# audio_mixer.net
KiCad netlist of a schematic drawn in EAGLE
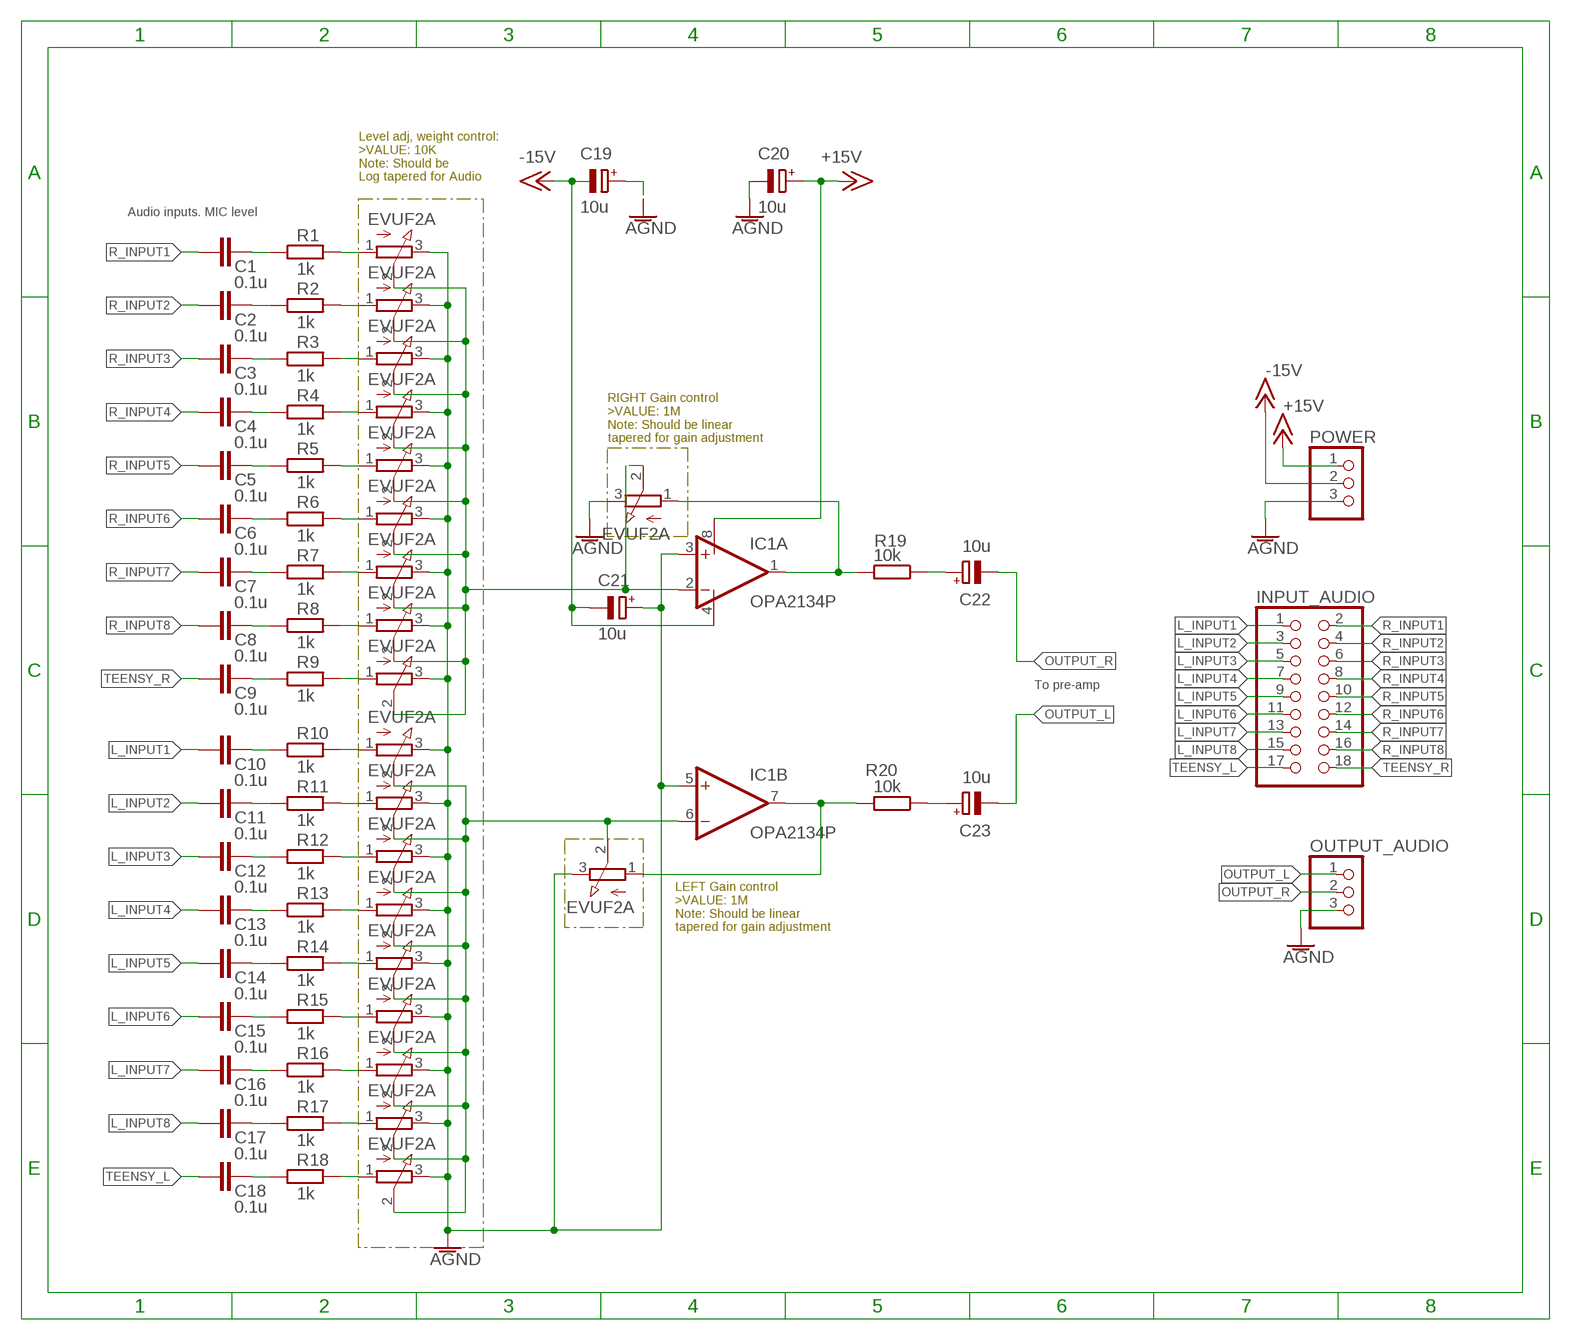
[diagram p0: schematic, sheet 1]

(export (version "E")
  (design (tool "Eeschema 10.0.6"))
  (components
    (comp (ref "C1")
      (value "0.1u")
      (footprint "eagle-import:C025-030X050")
      (libsource (lib "eagle-import") (part "C-EU025-030X050"))
    )
    (comp (ref "C2")
      (value "0.1u")
      (footprint "eagle-import:C025-030X050")
      (libsource (lib "eagle-import") (part "C-EU025-030X050"))
    )
    (comp (ref "C3")
      (value "0.1u")
      (footprint "eagle-import:C025-030X050")
      (libsource (lib "eagle-import") (part "C-EU025-030X050"))
    )
    (comp (ref "C4")
      (value "0.1u")
      (footprint "eagle-import:C025-030X050")
      (libsource (lib "eagle-import") (part "C-EU025-030X050"))
    )
    (comp (ref "C5")
      (value "0.1u")
      (footprint "eagle-import:C025-030X050")
      (libsource (lib "eagle-import") (part "C-EU025-030X050"))
    )
    (comp (ref "C6")
      (value "0.1u")
      (footprint "eagle-import:C025-030X050")
      (libsource (lib "eagle-import") (part "C-EU025-030X050"))
    )
    (comp (ref "C7")
      (value "0.1u")
      (footprint "eagle-import:C025-030X050")
      (libsource (lib "eagle-import") (part "C-EU025-030X050"))
    )
    (comp (ref "C8")
      (value "0.1u")
      (footprint "eagle-import:C025-030X050")
      (libsource (lib "eagle-import") (part "C-EU025-030X050"))
    )
    (comp (ref "C9")
      (value "0.1u")
      (footprint "eagle-import:C025-030X050")
      (libsource (lib "eagle-import") (part "C-EU025-030X050"))
    )
    (comp (ref "C10")
      (value "0.1u")
      (footprint "eagle-import:C025-030X050")
      (libsource (lib "eagle-import") (part "C-EU025-030X050"))
    )
    (comp (ref "C11")
      (value "0.1u")
      (footprint "eagle-import:C025-030X050")
      (libsource (lib "eagle-import") (part "C-EU025-030X050"))
    )
    (comp (ref "C12")
      (value "0.1u")
      (footprint "eagle-import:C025-030X050")
      (libsource (lib "eagle-import") (part "C-EU025-030X050"))
    )
    (comp (ref "C13")
      (value "0.1u")
      (footprint "eagle-import:C025-030X050")
      (libsource (lib "eagle-import") (part "C-EU025-030X050"))
    )
    (comp (ref "C14")
      (value "0.1u")
      (footprint "eagle-import:C025-030X050")
      (libsource (lib "eagle-import") (part "C-EU025-030X050"))
    )
    (comp (ref "C15")
      (value "0.1u")
      (footprint "eagle-import:C025-030X050")
      (libsource (lib "eagle-import") (part "C-EU025-030X050"))
    )
    (comp (ref "C16")
      (value "0.1u")
      (footprint "eagle-import:C025-030X050")
      (libsource (lib "eagle-import") (part "C-EU025-030X050"))
    )
    (comp (ref "C17")
      (value "0.1u")
      (footprint "eagle-import:C025-030X050")
      (libsource (lib "eagle-import") (part "C-EU025-030X050"))
    )
    (comp (ref "C18")
      (value "0.1u")
      (footprint "eagle-import:C025-030X050")
      (libsource (lib "eagle-import") (part "C-EU025-030X050"))
    )
    (comp (ref "C19")
      (value "10u")
      (footprint "eagle-import:E5-10,5")
      (libsource (lib "eagle-import") (part "CPOL-EUE5-10.5"))
    )
    (comp (ref "C20")
      (value "10u")
      (footprint "eagle-import:E5-10,5")
      (libsource (lib "eagle-import") (part "CPOL-EUE5-10.5"))
    )
    (comp (ref "C21")
      (value "10u")
      (footprint "eagle-import:E5-10,5")
      (libsource (lib "eagle-import") (part "CPOL-EUE5-10.5"))
    )
    (comp (ref "C22")
      (value "10u")
      (footprint "eagle-import:E5-10,5")
      (libsource (lib "eagle-import") (part "CPOL-EUE5-10.5"))
    )
    (comp (ref "C23")
      (value "10u")
      (footprint "eagle-import:E5-10,5")
      (libsource (lib "eagle-import") (part "CPOL-EUE5-10.5"))
    )
    (comp (ref "IC1")
      (value "OPA2134P")
      (footprint "eagle-import:DIL08")
      (libsource (lib "eagle-import") (part "OPA2134P"))
    )
    (comp (ref "INPUT_AUDIO")
      (value "PINHD-2X9")
      (footprint "eagle-import:2X09")
      (libsource (lib "eagle-import") (part "PINHD-2X9"))
    )
    (comp (ref "OUTPUT_AUDIO")
      (value "PINHD-1X3")
      (footprint "eagle-import:1X03")
      (libsource (lib "eagle-import") (part "PINHD-1X3"))
    )
    (comp (ref "POWER")
      (value "PINHD-1X3")
      (footprint "eagle-import:1X03")
      (libsource (lib "eagle-import") (part "PINHD-1X3"))
    )
    (comp (ref "R1")
      (value "1k")
      (footprint "eagle-import:R0805")
      (libsource (lib "eagle-import") (part "R-EU_R0805"))
    )
    (comp (ref "R2")
      (value "1k")
      (footprint "eagle-import:R0805")
      (libsource (lib "eagle-import") (part "R-EU_R0805"))
    )
    (comp (ref "R3")
      (value "1k")
      (footprint "eagle-import:R0805")
      (libsource (lib "eagle-import") (part "R-EU_R0805"))
    )
    (comp (ref "R4")
      (value "1k")
      (footprint "eagle-import:R0805")
      (libsource (lib "eagle-import") (part "R-EU_R0805"))
    )
    (comp (ref "R5")
      (value "1k")
      (footprint "eagle-import:R0805")
      (libsource (lib "eagle-import") (part "R-EU_R0805"))
    )
    (comp (ref "R6")
      (value "1k")
      (footprint "eagle-import:R0805")
      (libsource (lib "eagle-import") (part "R-EU_R0805"))
    )
    (comp (ref "R7")
      (value "1k")
      (footprint "eagle-import:R0805")
      (libsource (lib "eagle-import") (part "R-EU_R0805"))
    )
    (comp (ref "R8")
      (value "1k")
      (footprint "eagle-import:R0805")
      (libsource (lib "eagle-import") (part "R-EU_R0805"))
    )
    (comp (ref "R9")
      (value "1k")
      (footprint "eagle-import:R0805")
      (libsource (lib "eagle-import") (part "R-EU_R0805"))
    )
    (comp (ref "R10")
      (value "1k")
      (footprint "eagle-import:R0805")
      (libsource (lib "eagle-import") (part "R-EU_R0805"))
    )
    (comp (ref "R11")
      (value "1k")
      (footprint "eagle-import:R0805")
      (libsource (lib "eagle-import") (part "R-EU_R0805"))
    )
    (comp (ref "R12")
      (value "1k")
      (footprint "eagle-import:R0805")
      (libsource (lib "eagle-import") (part "R-EU_R0805"))
    )
    (comp (ref "R13")
      (value "1k")
      (footprint "eagle-import:R0805")
      (libsource (lib "eagle-import") (part "R-EU_R0805"))
    )
    (comp (ref "R14")
      (value "1k")
      (footprint "eagle-import:R0805")
      (libsource (lib "eagle-import") (part "R-EU_R0805"))
    )
    (comp (ref "R15")
      (value "1k")
      (footprint "eagle-import:R0805")
      (libsource (lib "eagle-import") (part "R-EU_R0805"))
    )
    (comp (ref "R16")
      (value "1k")
      (footprint "eagle-import:R0805")
      (libsource (lib "eagle-import") (part "R-EU_R0805"))
    )
    (comp (ref "R17")
      (value "1k")
      (footprint "eagle-import:R0805")
      (libsource (lib "eagle-import") (part "R-EU_R0805"))
    )
    (comp (ref "R18")
      (value "1k")
      (footprint "eagle-import:R0805")
      (libsource (lib "eagle-import") (part "R-EU_R0805"))
    )
    (comp (ref "R19")
      (value "10k")
      (footprint "eagle-import:R0805")
      (libsource (lib "eagle-import") (part "R-EU_R0805"))
    )
    (comp (ref "R20")
      (value "10k")
      (footprint "eagle-import:R0805")
      (libsource (lib "eagle-import") (part "R-EU_R0805"))
    )
    (comp (ref "VR1")
      (value "EVUF2A")
      (footprint "eagle-import:EVUF")
      (libsource (lib "eagle-import") (part "EVUAF2"))
    )
    (comp (ref "VR2")
      (value "EVUF2A")
      (footprint "eagle-import:EVUF")
      (libsource (lib "eagle-import") (part "EVUAF2"))
    )
    (comp (ref "VR3")
      (value "EVUF2A")
      (footprint "eagle-import:EVUF")
      (libsource (lib "eagle-import") (part "EVUAF2"))
    )
    (comp (ref "VR4")
      (value "EVUF2A")
      (footprint "eagle-import:EVUF")
      (libsource (lib "eagle-import") (part "EVUAF2"))
    )
    (comp (ref "VR5")
      (value "EVUF2A")
      (footprint "eagle-import:EVUF")
      (libsource (lib "eagle-import") (part "EVUAF2"))
    )
    (comp (ref "VR6")
      (value "EVUF2A")
      (footprint "eagle-import:EVUF")
      (libsource (lib "eagle-import") (part "EVUAF2"))
    )
    (comp (ref "VR7")
      (value "EVUF2A")
      (footprint "eagle-import:EVUF")
      (libsource (lib "eagle-import") (part "EVUAF2"))
    )
    (comp (ref "VR8")
      (value "EVUF2A")
      (footprint "eagle-import:EVUF")
      (libsource (lib "eagle-import") (part "EVUAF2"))
    )
    (comp (ref "VR9")
      (value "EVUF2A")
      (footprint "eagle-import:EVUF")
      (libsource (lib "eagle-import") (part "EVUAF2"))
    )
    (comp (ref "VR10")
      (value "EVUF2A")
      (footprint "eagle-import:EVUF")
      (libsource (lib "eagle-import") (part "EVUAF2"))
    )
    (comp (ref "VR11")
      (value "EVUF2A")
      (footprint "eagle-import:EVUF")
      (libsource (lib "eagle-import") (part "EVUAF2"))
    )
    (comp (ref "VR12")
      (value "EVUF2A")
      (footprint "eagle-import:EVUF")
      (libsource (lib "eagle-import") (part "EVUAF2"))
    )
    (comp (ref "VR13")
      (value "EVUF2A")
      (footprint "eagle-import:EVUF")
      (libsource (lib "eagle-import") (part "EVUAF2"))
    )
    (comp (ref "VR14")
      (value "EVUF2A")
      (footprint "eagle-import:EVUF")
      (libsource (lib "eagle-import") (part "EVUAF2"))
    )
    (comp (ref "VR15")
      (value "EVUF2A")
      (footprint "eagle-import:EVUF")
      (libsource (lib "eagle-import") (part "EVUAF2"))
    )
    (comp (ref "VR16")
      (value "EVUF2A")
      (footprint "eagle-import:EVUF")
      (libsource (lib "eagle-import") (part "EVUAF2"))
    )
    (comp (ref "VR17")
      (value "EVUF2A")
      (footprint "eagle-import:EVUF")
      (libsource (lib "eagle-import") (part "EVUAF2"))
    )
    (comp (ref "VR18")
      (value "EVUF2A")
      (footprint "eagle-import:EVUF")
      (libsource (lib "eagle-import") (part "EVUAF2"))
    )
    (comp (ref "VR19")
      (value "EVUF2A")
      (footprint "eagle-import:EVUF")
      (libsource (lib "eagle-import") (part "EVUAF2"))
    )
    (comp (ref "VR20")
      (value "EVUF2A")
      (footprint "eagle-import:EVUF")
      (libsource (lib "eagle-import") (part "EVUAF2"))
    )
  )
  (nets
    (net (code "1") (name "+15V") (class "Default")
      (node (ref "C20") (pin "+") (pinfunction "+_+") (pintype "passive"))
      (node (ref "IC1") (pin "8") (pinfunction "V+_8") (pintype "power_in"))
      (node (ref "POWER") (pin "1") (pinfunction "1_1") (pintype "passive"))
    )
    (net (code "2") (name "-15V") (class "Default")
      (node (ref "C19") (pin "-") (pinfunction "-_-") (pintype "passive"))
      (node (ref "C21") (pin "-") (pinfunction "-_-") (pintype "passive"))
      (node (ref "IC1") (pin "4") (pinfunction "V-_4") (pintype "power_in"))
      (node (ref "POWER") (pin "2") (pinfunction "2_2") (pintype "passive"))
    )
    (net (code "3") (name "AGND") (class "Default")
      (node (ref "C19") (pin "+") (pinfunction "+_+") (pintype "passive"))
      (node (ref "C20") (pin "-") (pinfunction "-_-") (pintype "passive"))
      (node (ref "C21") (pin "+") (pinfunction "+_+") (pintype "passive"))
      (node (ref "IC1") (pin "3") (pinfunction "+IN_3") (pintype "input"))
      (node (ref "IC1") (pin "5") (pinfunction "+IN_5") (pintype "input"))
      (node (ref "OUTPUT_AUDIO") (pin "3") (pinfunction "3_3") (pintype "passive"))
      (node (ref "POWER") (pin "3") (pinfunction "3_3") (pintype "passive"))
      (node (ref "VR1") (pin "3") (pinfunction "E_3") (pintype "passive"))
      (node (ref "VR10") (pin "3") (pinfunction "E_3") (pintype "passive"))
      (node (ref "VR11") (pin "3") (pinfunction "E_3") (pintype "passive"))
      (node (ref "VR12") (pin "3") (pinfunction "E_3") (pintype "passive"))
      (node (ref "VR13") (pin "3") (pinfunction "E_3") (pintype "passive"))
      (node (ref "VR14") (pin "3") (pinfunction "E_3") (pintype "passive"))
      (node (ref "VR15") (pin "3") (pinfunction "E_3") (pintype "passive"))
      (node (ref "VR16") (pin "3") (pinfunction "E_3") (pintype "passive"))
      (node (ref "VR17") (pin "3") (pinfunction "E_3") (pintype "passive"))
      (node (ref "VR18") (pin "3") (pinfunction "E_3") (pintype "passive"))
      (node (ref "VR19") (pin "3") (pinfunction "E_3") (pintype "passive"))
      (node (ref "VR2") (pin "3") (pinfunction "E_3") (pintype "passive"))
      (node (ref "VR20") (pin "3") (pinfunction "E_3") (pintype "passive"))
      (node (ref "VR3") (pin "3") (pinfunction "E_3") (pintype "passive"))
      (node (ref "VR4") (pin "3") (pinfunction "E_3") (pintype "passive"))
      (node (ref "VR5") (pin "3") (pinfunction "E_3") (pintype "passive"))
      (node (ref "VR6") (pin "3") (pinfunction "E_3") (pintype "passive"))
      (node (ref "VR7") (pin "3") (pinfunction "E_3") (pintype "passive"))
      (node (ref "VR8") (pin "3") (pinfunction "E_3") (pintype "passive"))
      (node (ref "VR9") (pin "3") (pinfunction "E_3") (pintype "passive"))
    )
    (net (code "4") (name "L_INPUT1") (class "Default")
      (node (ref "C10") (pin "2") (pinfunction "2_2") (pintype "passive"))
      (node (ref "INPUT_AUDIO") (pin "1") (pinfunction "1_1") (pintype "passive"))
    )
    (net (code "5") (name "L_INPUT2") (class "Default")
      (node (ref "C11") (pin "2") (pinfunction "2_2") (pintype "passive"))
      (node (ref "INPUT_AUDIO") (pin "3") (pinfunction "3_3") (pintype "passive"))
    )
    (net (code "6") (name "L_INPUT3") (class "Default")
      (node (ref "C12") (pin "2") (pinfunction "2_2") (pintype "passive"))
      (node (ref "INPUT_AUDIO") (pin "5") (pinfunction "5_5") (pintype "passive"))
    )
    (net (code "7") (name "L_INPUT4") (class "Default")
      (node (ref "C13") (pin "2") (pinfunction "2_2") (pintype "passive"))
      (node (ref "INPUT_AUDIO") (pin "7") (pinfunction "7_7") (pintype "passive"))
    )
    (net (code "8") (name "L_INPUT5") (class "Default")
      (node (ref "C14") (pin "2") (pinfunction "2_2") (pintype "passive"))
      (node (ref "INPUT_AUDIO") (pin "9") (pinfunction "9_9") (pintype "passive"))
    )
    (net (code "9") (name "L_INPUT6") (class "Default")
      (node (ref "C15") (pin "2") (pinfunction "2_2") (pintype "passive"))
      (node (ref "INPUT_AUDIO") (pin "11") (pinfunction "11_11") (pintype "passive"))
    )
    (net (code "10") (name "L_INPUT7") (class "Default")
      (node (ref "C16") (pin "2") (pinfunction "2_2") (pintype "passive"))
      (node (ref "INPUT_AUDIO") (pin "13") (pinfunction "13_13") (pintype "passive"))
    )
    (net (code "11") (name "L_INPUT8") (class "Default")
      (node (ref "C17") (pin "2") (pinfunction "2_2") (pintype "passive"))
      (node (ref "INPUT_AUDIO") (pin "15") (pinfunction "15_15") (pintype "passive"))
    )
    (net (code "12") (name "Net-(C1-Pad1)") (class "Default")
      (node (ref "C1") (pin "1") (pinfunction "1_1") (pintype "passive"))
      (node (ref "R1") (pin "1") (pinfunction "1_1") (pintype "passive"))
    )
    (net (code "13") (name "Net-(C2-Pad1)") (class "Default")
      (node (ref "C2") (pin "1") (pinfunction "1_1") (pintype "passive"))
      (node (ref "R2") (pin "1") (pinfunction "1_1") (pintype "passive"))
    )
    (net (code "14") (name "Net-(C3-Pad1)") (class "Default")
      (node (ref "C3") (pin "1") (pinfunction "1_1") (pintype "passive"))
      (node (ref "R3") (pin "1") (pinfunction "1_1") (pintype "passive"))
    )
    (net (code "15") (name "Net-(C4-Pad1)") (class "Default")
      (node (ref "C4") (pin "1") (pinfunction "1_1") (pintype "passive"))
      (node (ref "R4") (pin "1") (pinfunction "1_1") (pintype "passive"))
    )
    (net (code "16") (name "Net-(C5-Pad1)") (class "Default")
      (node (ref "C5") (pin "1") (pinfunction "1_1") (pintype "passive"))
      (node (ref "R5") (pin "1") (pinfunction "1_1") (pintype "passive"))
    )
    (net (code "17") (name "Net-(C6-Pad1)") (class "Default")
      (node (ref "C6") (pin "1") (pinfunction "1_1") (pintype "passive"))
      (node (ref "R6") (pin "1") (pinfunction "1_1") (pintype "passive"))
    )
    (net (code "18") (name "Net-(C7-Pad1)") (class "Default")
      (node (ref "C7") (pin "1") (pinfunction "1_1") (pintype "passive"))
      (node (ref "R7") (pin "1") (pinfunction "1_1") (pintype "passive"))
    )
    (net (code "19") (name "Net-(C8-Pad1)") (class "Default")
      (node (ref "C8") (pin "1") (pinfunction "1_1") (pintype "passive"))
      (node (ref "R8") (pin "1") (pinfunction "1_1") (pintype "passive"))
    )
    (net (code "20") (name "Net-(C9-Pad1)") (class "Default")
      (node (ref "C9") (pin "1") (pinfunction "1_1") (pintype "passive"))
      (node (ref "R9") (pin "1") (pinfunction "1_1") (pintype "passive"))
    )
    (net (code "21") (name "Net-(C10-Pad1)") (class "Default")
      (node (ref "C10") (pin "1") (pinfunction "1_1") (pintype "passive"))
      (node (ref "R10") (pin "1") (pinfunction "1_1") (pintype "passive"))
    )
    (net (code "22") (name "Net-(C11-Pad1)") (class "Default")
      (node (ref "C11") (pin "1") (pinfunction "1_1") (pintype "passive"))
      (node (ref "R11") (pin "1") (pinfunction "1_1") (pintype "passive"))
    )
    (net (code "23") (name "Net-(C12-Pad1)") (class "Default")
      (node (ref "C12") (pin "1") (pinfunction "1_1") (pintype "passive"))
      (node (ref "R12") (pin "1") (pinfunction "1_1") (pintype "passive"))
    )
    (net (code "24") (name "Net-(C13-Pad1)") (class "Default")
      (node (ref "C13") (pin "1") (pinfunction "1_1") (pintype "passive"))
      (node (ref "R13") (pin "1") (pinfunction "1_1") (pintype "passive"))
    )
    (net (code "25") (name "Net-(C14-Pad1)") (class "Default")
      (node (ref "C14") (pin "1") (pinfunction "1_1") (pintype "passive"))
      (node (ref "R14") (pin "1") (pinfunction "1_1") (pintype "passive"))
    )
    (net (code "26") (name "Net-(C15-Pad1)") (class "Default")
      (node (ref "C15") (pin "1") (pinfunction "1_1") (pintype "passive"))
      (node (ref "R15") (pin "1") (pinfunction "1_1") (pintype "passive"))
    )
    (net (code "27") (name "Net-(C16-Pad1)") (class "Default")
      (node (ref "C16") (pin "1") (pinfunction "1_1") (pintype "passive"))
      (node (ref "R16") (pin "1") (pinfunction "1_1") (pintype "passive"))
    )
    (net (code "28") (name "Net-(C17-Pad1)") (class "Default")
      (node (ref "C17") (pin "1") (pinfunction "1_1") (pintype "passive"))
      (node (ref "R17") (pin "1") (pinfunction "1_1") (pintype "passive"))
    )
    (net (code "29") (name "Net-(C18-Pad1)") (class "Default")
      (node (ref "C18") (pin "1") (pinfunction "1_1") (pintype "passive"))
      (node (ref "R18") (pin "1") (pinfunction "1_1") (pintype "passive"))
    )
    (net (code "30") (name "Net-(C22-Pad+)") (class "Default")
      (node (ref "C22") (pin "+") (pinfunction "+_+") (pintype "passive"))
      (node (ref "R19") (pin "1") (pinfunction "1_1") (pintype "passive"))
    )
    (net (code "31") (name "Net-(C23-Pad+)") (class "Default")
      (node (ref "C23") (pin "+") (pinfunction "+_+") (pintype "passive"))
      (node (ref "R20") (pin "1") (pinfunction "1_1") (pintype "passive"))
    )
    (net (code "32") (name "Net-(IC1A--IN)") (class "Default")
      (node (ref "IC1") (pin "2") (pinfunction "-IN_2") (pintype "input"))
      (node (ref "VR1") (pin "2") (pinfunction "S_2") (pintype "passive"))
      (node (ref "VR19") (pin "2") (pinfunction "S_2") (pintype "passive"))
      (node (ref "VR2") (pin "2") (pinfunction "S_2") (pintype "passive"))
      (node (ref "VR3") (pin "2") (pinfunction "S_2") (pintype "passive"))
      (node (ref "VR4") (pin "2") (pinfunction "S_2") (pintype "passive"))
      (node (ref "VR5") (pin "2") (pinfunction "S_2") (pintype "passive"))
      (node (ref "VR6") (pin "2") (pinfunction "S_2") (pintype "passive"))
      (node (ref "VR7") (pin "2") (pinfunction "S_2") (pintype "passive"))
      (node (ref "VR8") (pin "2") (pinfunction "S_2") (pintype "passive"))
      (node (ref "VR9") (pin "2") (pinfunction "S_2") (pintype "passive"))
    )
    (net (code "33") (name "Net-(IC1A-OUT)") (class "Default")
      (node (ref "IC1") (pin "1") (pinfunction "OUT_1") (pintype "output"))
      (node (ref "R19") (pin "2") (pinfunction "2_2") (pintype "passive"))
      (node (ref "VR19") (pin "1") (pinfunction "A_1") (pintype "passive"))
    )
    (net (code "34") (name "Net-(IC1B--IN)") (class "Default")
      (node (ref "IC1") (pin "6") (pinfunction "-IN_6") (pintype "input"))
      (node (ref "VR10") (pin "2") (pinfunction "S_2") (pintype "passive"))
      (node (ref "VR11") (pin "2") (pinfunction "S_2") (pintype "passive"))
      (node (ref "VR12") (pin "2") (pinfunction "S_2") (pintype "passive"))
      (node (ref "VR13") (pin "2") (pinfunction "S_2") (pintype "passive"))
      (node (ref "VR14") (pin "2") (pinfunction "S_2") (pintype "passive"))
      (node (ref "VR15") (pin "2") (pinfunction "S_2") (pintype "passive"))
      (node (ref "VR16") (pin "2") (pinfunction "S_2") (pintype "passive"))
      (node (ref "VR17") (pin "2") (pinfunction "S_2") (pintype "passive"))
      (node (ref "VR18") (pin "2") (pinfunction "S_2") (pintype "passive"))
      (node (ref "VR20") (pin "2") (pinfunction "S_2") (pintype "passive"))
    )
    (net (code "35") (name "Net-(IC1B-OUT)") (class "Default")
      (node (ref "IC1") (pin "7") (pinfunction "OUT_7") (pintype "output"))
      (node (ref "R20") (pin "2") (pinfunction "2_2") (pintype "passive"))
      (node (ref "VR20") (pin "1") (pinfunction "A_1") (pintype "passive"))
    )
    (net (code "36") (name "Net-(VR1-A)") (class "Default")
      (node (ref "R1") (pin "2") (pinfunction "2_2") (pintype "passive"))
      (node (ref "VR1") (pin "1") (pinfunction "A_1") (pintype "passive"))
    )
    (net (code "37") (name "Net-(VR2-A)") (class "Default")
      (node (ref "R2") (pin "2") (pinfunction "2_2") (pintype "passive"))
      (node (ref "VR2") (pin "1") (pinfunction "A_1") (pintype "passive"))
    )
    (net (code "38") (name "Net-(VR3-A)") (class "Default")
      (node (ref "R3") (pin "2") (pinfunction "2_2") (pintype "passive"))
      (node (ref "VR3") (pin "1") (pinfunction "A_1") (pintype "passive"))
    )
    (net (code "39") (name "Net-(VR4-A)") (class "Default")
      (node (ref "R4") (pin "2") (pinfunction "2_2") (pintype "passive"))
      (node (ref "VR4") (pin "1") (pinfunction "A_1") (pintype "passive"))
    )
    (net (code "40") (name "Net-(VR5-A)") (class "Default")
      (node (ref "R5") (pin "2") (pinfunction "2_2") (pintype "passive"))
      (node (ref "VR5") (pin "1") (pinfunction "A_1") (pintype "passive"))
    )
    (net (code "41") (name "Net-(VR6-A)") (class "Default")
      (node (ref "R6") (pin "2") (pinfunction "2_2") (pintype "passive"))
      (node (ref "VR6") (pin "1") (pinfunction "A_1") (pintype "passive"))
    )
    (net (code "42") (name "Net-(VR7-A)") (class "Default")
      (node (ref "R7") (pin "2") (pinfunction "2_2") (pintype "passive"))
      (node (ref "VR7") (pin "1") (pinfunction "A_1") (pintype "passive"))
    )
    (net (code "43") (name "Net-(VR8-A)") (class "Default")
      (node (ref "R8") (pin "2") (pinfunction "2_2") (pintype "passive"))
      (node (ref "VR8") (pin "1") (pinfunction "A_1") (pintype "passive"))
    )
    (net (code "44") (name "Net-(VR9-A)") (class "Default")
      (node (ref "R9") (pin "2") (pinfunction "2_2") (pintype "passive"))
      (node (ref "VR9") (pin "1") (pinfunction "A_1") (pintype "passive"))
    )
    (net (code "45") (name "Net-(VR10-A)") (class "Default")
      (node (ref "R10") (pin "2") (pinfunction "2_2") (pintype "passive"))
      (node (ref "VR10") (pin "1") (pinfunction "A_1") (pintype "passive"))
    )
    (net (code "46") (name "Net-(VR11-A)") (class "Default")
      (node (ref "R11") (pin "2") (pinfunction "2_2") (pintype "passive"))
      (node (ref "VR11") (pin "1") (pinfunction "A_1") (pintype "passive"))
    )
    (net (code "47") (name "Net-(VR12-A)") (class "Default")
      (node (ref "R12") (pin "2") (pinfunction "2_2") (pintype "passive"))
      (node (ref "VR12") (pin "1") (pinfunction "A_1") (pintype "passive"))
    )
    (net (code "48") (name "Net-(VR13-A)") (class "Default")
      (node (ref "R13") (pin "2") (pinfunction "2_2") (pintype "passive"))
      (node (ref "VR13") (pin "1") (pinfunction "A_1") (pintype "passive"))
    )
    (net (code "49") (name "Net-(VR14-A)") (class "Default")
      (node (ref "R14") (pin "2") (pinfunction "2_2") (pintype "passive"))
      (node (ref "VR14") (pin "1") (pinfunction "A_1") (pintype "passive"))
    )
    (net (code "50") (name "Net-(VR15-A)") (class "Default")
      (node (ref "R15") (pin "2") (pinfunction "2_2") (pintype "passive"))
      (node (ref "VR15") (pin "1") (pinfunction "A_1") (pintype "passive"))
    )
    (net (code "51") (name "Net-(VR16-A)") (class "Default")
      (node (ref "R16") (pin "2") (pinfunction "2_2") (pintype "passive"))
      (node (ref "VR16") (pin "1") (pinfunction "A_1") (pintype "passive"))
    )
    (net (code "52") (name "Net-(VR17-A)") (class "Default")
      (node (ref "R17") (pin "2") (pinfunction "2_2") (pintype "passive"))
      (node (ref "VR17") (pin "1") (pinfunction "A_1") (pintype "passive"))
    )
    (net (code "53") (name "Net-(VR18-A)") (class "Default")
      (node (ref "R18") (pin "2") (pinfunction "2_2") (pintype "passive"))
      (node (ref "VR18") (pin "1") (pinfunction "A_1") (pintype "passive"))
    )
    (net (code "54") (name "OUTPUT_L") (class "Default")
      (node (ref "C23") (pin "-") (pinfunction "-_-") (pintype "passive"))
      (node (ref "OUTPUT_AUDIO") (pin "1") (pinfunction "1_1") (pintype "passive"))
    )
    (net (code "55") (name "OUTPUT_R") (class "Default")
      (node (ref "C22") (pin "-") (pinfunction "-_-") (pintype "passive"))
      (node (ref "OUTPUT_AUDIO") (pin "2") (pinfunction "2_2") (pintype "passive"))
    )
    (net (code "56") (name "R_INPUT1") (class "Default")
      (node (ref "C1") (pin "2") (pinfunction "2_2") (pintype "passive"))
      (node (ref "INPUT_AUDIO") (pin "2") (pinfunction "2_2") (pintype "passive"))
    )
    (net (code "57") (name "R_INPUT2") (class "Default")
      (node (ref "C2") (pin "2") (pinfunction "2_2") (pintype "passive"))
      (node (ref "INPUT_AUDIO") (pin "4") (pinfunction "4_4") (pintype "passive"))
    )
    (net (code "58") (name "R_INPUT3") (class "Default")
      (node (ref "C3") (pin "2") (pinfunction "2_2") (pintype "passive"))
      (node (ref "INPUT_AUDIO") (pin "6") (pinfunction "6_6") (pintype "passive"))
    )
    (net (code "59") (name "R_INPUT4") (class "Default")
      (node (ref "C4") (pin "2") (pinfunction "2_2") (pintype "passive"))
      (node (ref "INPUT_AUDIO") (pin "8") (pinfunction "8_8") (pintype "passive"))
    )
    (net (code "60") (name "R_INPUT5") (class "Default")
      (node (ref "C5") (pin "2") (pinfunction "2_2") (pintype "passive"))
      (node (ref "INPUT_AUDIO") (pin "10") (pinfunction "10_10") (pintype "passive"))
    )
    (net (code "61") (name "R_INPUT6") (class "Default")
      (node (ref "C6") (pin "2") (pinfunction "2_2") (pintype "passive"))
      (node (ref "INPUT_AUDIO") (pin "12") (pinfunction "12_12") (pintype "passive"))
    )
    (net (code "62") (name "R_INPUT7") (class "Default")
      (node (ref "C7") (pin "2") (pinfunction "2_2") (pintype "passive"))
      (node (ref "INPUT_AUDIO") (pin "14") (pinfunction "14_14") (pintype "passive"))
    )
    (net (code "63") (name "R_INPUT8") (class "Default")
      (node (ref "C8") (pin "2") (pinfunction "2_2") (pintype "passive"))
      (node (ref "INPUT_AUDIO") (pin "16") (pinfunction "16_16") (pintype "passive"))
    )
    (net (code "64") (name "TEENSY_L") (class "Default")
      (node (ref "C18") (pin "2") (pinfunction "2_2") (pintype "passive"))
      (node (ref "INPUT_AUDIO") (pin "17") (pinfunction "17_17") (pintype "passive"))
    )
    (net (code "65") (name "TEENSY_R") (class "Default")
      (node (ref "C9") (pin "2") (pinfunction "2_2") (pintype "passive"))
      (node (ref "INPUT_AUDIO") (pin "18") (pinfunction "18_18") (pintype "passive"))
    )
  )
)
